# CMOS_Trumpet.net
KiCad netlist of a schematic drawn in EAGLE
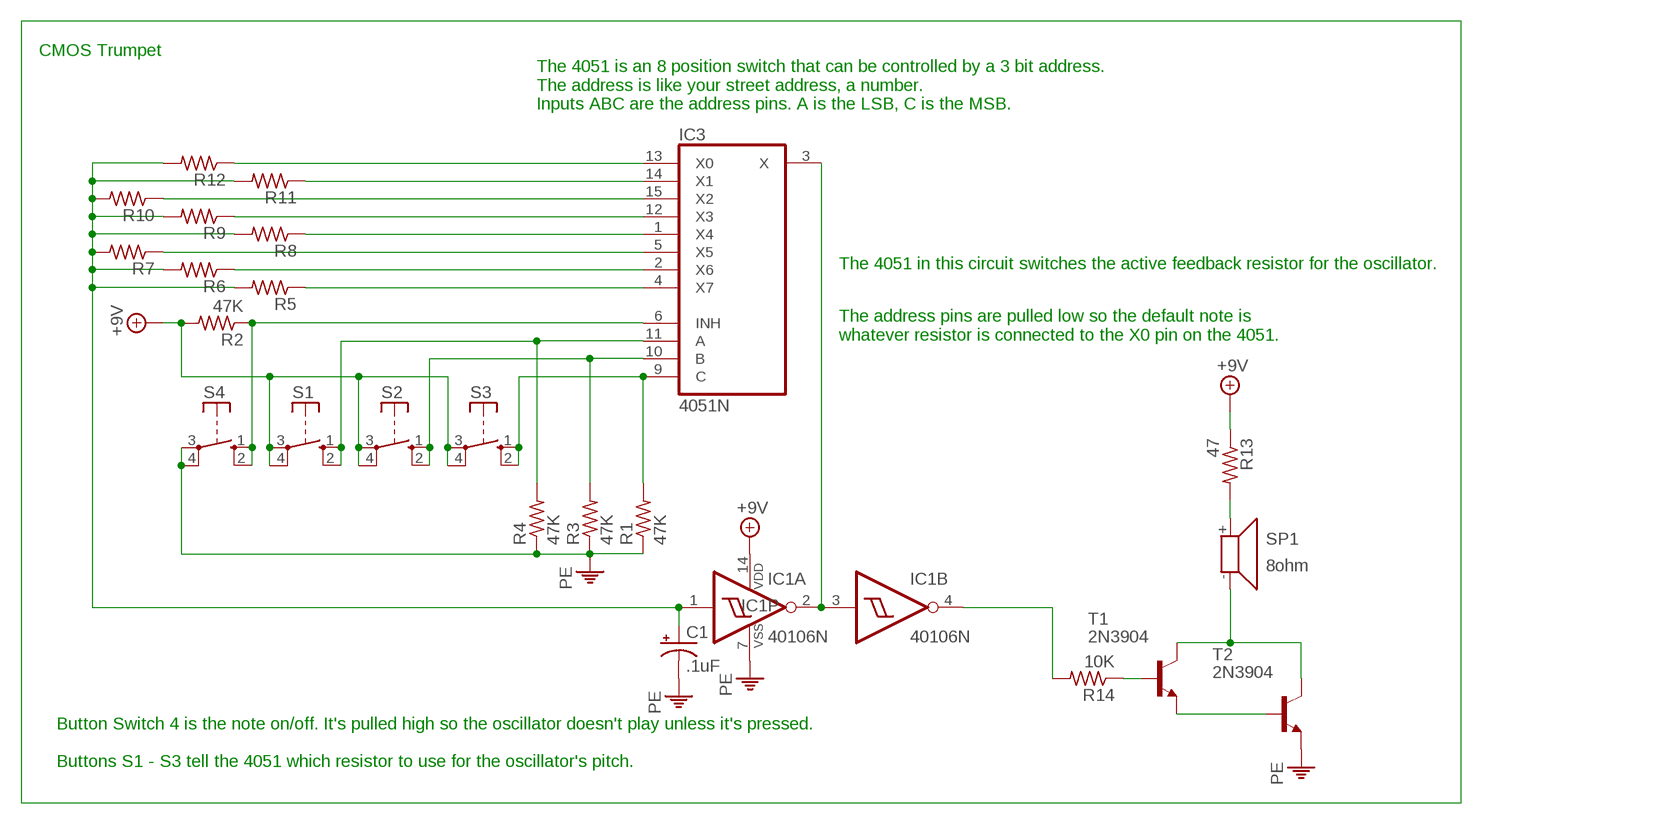
[diagram p0: schematic, sheet 1]

(export (version "E")
  (design (tool "Eeschema 10.0.6"))
  (components
    (comp (ref "C1")
      (value ".1uF")
      (footprint "eagle-import:E2,5-6E")
      (libsource (lib "eagle-import") (part "CPOL-USE2,5-6E"))
    )
    (comp (ref "IC1")
      (value "40106N")
      (footprint "eagle-import:DIL14")
      (libsource (lib "eagle-import") (part "40106N"))
    )
    (comp (ref "IC3")
      (value "4051N")
      (footprint "eagle-import:DIL16")
      (libsource (lib "eagle-import") (part "4051N"))
    )
    (comp (ref "R1")
      (value "47K")
      (footprint "eagle-import:0204_7")
      (libsource (lib "eagle-import") (part "R-US_0204/7"))
    )
    (comp (ref "R2")
      (value "47K")
      (footprint "eagle-import:0204_7")
      (libsource (lib "eagle-import") (part "R-US_0204/7"))
    )
    (comp (ref "R3")
      (value "47K")
      (footprint "eagle-import:0204_7")
      (libsource (lib "eagle-import") (part "R-US_0204/7"))
    )
    (comp (ref "R4")
      (value "47K")
      (footprint "eagle-import:0204_7")
      (libsource (lib "eagle-import") (part "R-US_0204/7"))
    )
    (comp (ref "R5")
      (value "R-US_0204/7")
      (footprint "eagle-import:0204_7")
      (libsource (lib "eagle-import") (part "R-US_0204/7"))
    )
    (comp (ref "R6")
      (value "R-US_0204/7")
      (footprint "eagle-import:0204_7")
      (libsource (lib "eagle-import") (part "R-US_0204/7"))
    )
    (comp (ref "R7")
      (value "R-US_0204/7")
      (footprint "eagle-import:0204_7")
      (libsource (lib "eagle-import") (part "R-US_0204/7"))
    )
    (comp (ref "R8")
      (value "R-US_0204/7")
      (footprint "eagle-import:0204_7")
      (libsource (lib "eagle-import") (part "R-US_0204/7"))
    )
    (comp (ref "R9")
      (value "R-US_0204/7")
      (footprint "eagle-import:0204_7")
      (libsource (lib "eagle-import") (part "R-US_0204/7"))
    )
    (comp (ref "R10")
      (value "R-US_0204/7")
      (footprint "eagle-import:0204_7")
      (libsource (lib "eagle-import") (part "R-US_0204/7"))
    )
    (comp (ref "R11")
      (value "R-US_0204/7")
      (footprint "eagle-import:0204_7")
      (libsource (lib "eagle-import") (part "R-US_0204/7"))
    )
    (comp (ref "R12")
      (value "R-US_0204/7")
      (footprint "eagle-import:0204_7")
      (libsource (lib "eagle-import") (part "R-US_0204/7"))
    )
    (comp (ref "R13")
      (value "47")
      (footprint "eagle-import:0204_7")
      (libsource (lib "eagle-import") (part "R-US_0204/7"))
    )
    (comp (ref "R14")
      (value "10K")
      (footprint "eagle-import:0204_7")
      (libsource (lib "eagle-import") (part "R-US_0204/7"))
    )
    (comp (ref "S1")
      (value "RACON12")
      (footprint "eagle-import:RACON12")
      (libsource (lib "eagle-import") (part "RACON12"))
    )
    (comp (ref "S2")
      (value "RACON12")
      (footprint "eagle-import:RACON12")
      (libsource (lib "eagle-import") (part "RACON12"))
    )
    (comp (ref "S3")
      (value "RACON12")
      (footprint "eagle-import:RACON12")
      (libsource (lib "eagle-import") (part "RACON12"))
    )
    (comp (ref "S4")
      (value "RACON12")
      (footprint "eagle-import:RACON12")
      (libsource (lib "eagle-import") (part "RACON12"))
    )
    (comp (ref "SP1")
      (value "8ohm")
      (footprint "eagle-import:SMS-1308MS-2-R")
      (libsource (lib "eagle-import") (part "SMS-1308MS-2-R"))
    )
    (comp (ref "T1")
      (value "2N3904")
      (footprint "eagle-import:TO92")
      (libsource (lib "eagle-import") (part "2N3904"))
    )
    (comp (ref "T2")
      (value "2N3904")
      (footprint "eagle-import:TO92")
      (libsource (lib "eagle-import") (part "2N3904"))
    )
  )
  (nets
    (net (code "1") (name "+9V") (class "Default")
      (node (ref "IC1") (pin "14") (pinfunction "VDD_14") (pintype "power_in"))
      (node (ref "R13") (pin "1") (pinfunction "1_1") (pintype "passive"))
      (node (ref "R2") (pin "2") (pinfunction "2_2") (pintype "passive"))
      (node (ref "S1") (pin "3") (pinfunction "P_3") (pintype "passive"))
      (node (ref "S1") (pin "4") (pinfunction "P_4") (pintype "passive"))
      (node (ref "S2") (pin "3") (pinfunction "P_3") (pintype "passive"))
      (node (ref "S2") (pin "4") (pinfunction "P_4") (pintype "passive"))
      (node (ref "S3") (pin "3") (pinfunction "P_3") (pintype "passive"))
      (node (ref "S3") (pin "4") (pinfunction "P_4") (pintype "passive"))
    )
    (net (code "2") (name "Net-(IC1A-I)") (class "Default")
      (node (ref "C1") (pin "+") (pinfunction "+_+") (pintype "passive"))
      (node (ref "IC1") (pin "1") (pinfunction "I_1") (pintype "input"))
      (node (ref "R10") (pin "2") (pinfunction "2_2") (pintype "passive"))
      (node (ref "R11") (pin "2") (pinfunction "2_2") (pintype "passive"))
      (node (ref "R12") (pin "2") (pinfunction "2_2") (pintype "passive"))
      (node (ref "R5") (pin "2") (pinfunction "2_2") (pintype "passive"))
      (node (ref "R6") (pin "2") (pinfunction "2_2") (pintype "passive"))
      (node (ref "R7") (pin "2") (pinfunction "2_2") (pintype "passive"))
      (node (ref "R8") (pin "2") (pinfunction "2_2") (pintype "passive"))
      (node (ref "R9") (pin "2") (pinfunction "2_2") (pintype "passive"))
    )
    (net (code "3") (name "Net-(IC1A-O)") (class "Default")
      (node (ref "IC1") (pin "2") (pinfunction "O_2") (pintype "output"))
      (node (ref "IC1") (pin "3") (pinfunction "I_3") (pintype "input"))
      (node (ref "IC3") (pin "3") (pinfunction "X_3") (pintype "bidirectional"))
    )
    (net (code "4") (name "Net-(IC1B-O)") (class "Default")
      (node (ref "IC1") (pin "4") (pinfunction "O_4") (pintype "output"))
      (node (ref "R14") (pin "2") (pinfunction "2_2") (pintype "passive"))
    )
    (net (code "5") (name "Net-(IC3A-A)") (class "Default")
      (node (ref "IC3") (pin "11") (pinfunction "A_11") (pintype "input"))
      (node (ref "R4") (pin "2") (pinfunction "2_2") (pintype "passive"))
      (node (ref "S1") (pin "1") (pinfunction "S_1") (pintype "passive"))
      (node (ref "S1") (pin "2") (pinfunction "S_2") (pintype "passive"))
    )
    (net (code "6") (name "Net-(IC3A-B)") (class "Default")
      (node (ref "IC3") (pin "10") (pinfunction "B_10") (pintype "input"))
      (node (ref "R3") (pin "2") (pinfunction "2_2") (pintype "passive"))
      (node (ref "S2") (pin "1") (pinfunction "S_1") (pintype "passive"))
      (node (ref "S2") (pin "2") (pinfunction "S_2") (pintype "passive"))
    )
    (net (code "7") (name "Net-(IC3A-C)") (class "Default")
      (node (ref "IC3") (pin "9") (pinfunction "C_9") (pintype "input"))
      (node (ref "R1") (pin "2") (pinfunction "2_2") (pintype "passive"))
      (node (ref "S3") (pin "1") (pinfunction "S_1") (pintype "passive"))
      (node (ref "S3") (pin "2") (pinfunction "S_2") (pintype "passive"))
    )
    (net (code "8") (name "Net-(IC3A-INH)") (class "Default")
      (node (ref "IC3") (pin "6") (pinfunction "INH_6") (pintype "input"))
      (node (ref "R2") (pin "1") (pinfunction "1_1") (pintype "passive"))
      (node (ref "S4") (pin "1") (pinfunction "S_1") (pintype "passive"))
      (node (ref "S4") (pin "2") (pinfunction "S_2") (pintype "passive"))
    )
    (net (code "9") (name "Net-(IC3A-X0)") (class "Default")
      (node (ref "IC3") (pin "13") (pinfunction "X0_13") (pintype "bidirectional"))
      (node (ref "R12") (pin "1") (pinfunction "1_1") (pintype "passive"))
    )
    (net (code "10") (name "Net-(IC3A-X1)") (class "Default")
      (node (ref "IC3") (pin "14") (pinfunction "X1_14") (pintype "bidirectional"))
      (node (ref "R11") (pin "1") (pinfunction "1_1") (pintype "passive"))
    )
    (net (code "11") (name "Net-(IC3A-X2)") (class "Default")
      (node (ref "IC3") (pin "15") (pinfunction "X2_15") (pintype "bidirectional"))
      (node (ref "R10") (pin "1") (pinfunction "1_1") (pintype "passive"))
    )
    (net (code "12") (name "Net-(IC3A-X3)") (class "Default")
      (node (ref "IC3") (pin "12") (pinfunction "X3_12") (pintype "bidirectional"))
      (node (ref "R9") (pin "1") (pinfunction "1_1") (pintype "passive"))
    )
    (net (code "13") (name "Net-(IC3A-X4)") (class "Default")
      (node (ref "IC3") (pin "1") (pinfunction "X4_1") (pintype "bidirectional"))
      (node (ref "R8") (pin "1") (pinfunction "1_1") (pintype "passive"))
    )
    (net (code "14") (name "Net-(IC3A-X5)") (class "Default")
      (node (ref "IC3") (pin "5") (pinfunction "X5_5") (pintype "bidirectional"))
      (node (ref "R7") (pin "1") (pinfunction "1_1") (pintype "passive"))
    )
    (net (code "15") (name "Net-(IC3A-X6)") (class "Default")
      (node (ref "IC3") (pin "2") (pinfunction "X6_2") (pintype "bidirectional"))
      (node (ref "R6") (pin "1") (pinfunction "1_1") (pintype "passive"))
    )
    (net (code "16") (name "Net-(IC3A-X7)") (class "Default")
      (node (ref "IC3") (pin "4") (pinfunction "X7_4") (pintype "bidirectional"))
      (node (ref "R5") (pin "1") (pinfunction "1_1") (pintype "passive"))
    )
    (net (code "17") (name "Net-(SP1-1)") (class "Default")
      (node (ref "R13") (pin "2") (pinfunction "2_2") (pintype "passive"))
      (node (ref "SP1") (pin "+") (pinfunction "1_+") (pintype "passive"))
    )
    (net (code "18") (name "Net-(SP1-2)") (class "Default")
      (node (ref "SP1") (pin "-") (pinfunction "2_-") (pintype "passive"))
      (node (ref "T1") (pin "1") (pinfunction "C_1") (pintype "passive"))
      (node (ref "T2") (pin "1") (pinfunction "C_1") (pintype "passive"))
    )
    (net (code "19") (name "Net-(T1-B)") (class "Default")
      (node (ref "R14") (pin "1") (pinfunction "1_1") (pintype "passive"))
      (node (ref "T1") (pin "2") (pinfunction "B_2") (pintype "passive"))
    )
    (net (code "20") (name "Net-(T1-E)") (class "Default")
      (node (ref "T1") (pin "3") (pinfunction "E_3") (pintype "passive"))
      (node (ref "T2") (pin "2") (pinfunction "B_2") (pintype "passive"))
    )
    (net (code "21") (name "PE") (class "Default")
      (node (ref "C1") (pin "-") (pinfunction "-_-") (pintype "passive"))
      (node (ref "IC1") (pin "7") (pinfunction "VSS_7") (pintype "power_in"))
      (node (ref "R1") (pin "1") (pinfunction "1_1") (pintype "passive"))
      (node (ref "R3") (pin "1") (pinfunction "1_1") (pintype "passive"))
      (node (ref "R4") (pin "1") (pinfunction "1_1") (pintype "passive"))
      (node (ref "S4") (pin "3") (pinfunction "P_3") (pintype "passive"))
      (node (ref "S4") (pin "4") (pinfunction "P_4") (pintype "passive"))
      (node (ref "T2") (pin "3") (pinfunction "E_3") (pintype "passive"))
    )
  )
)
